# CAN.net
KiCad netlist of a schematic drawn in Altium Designer
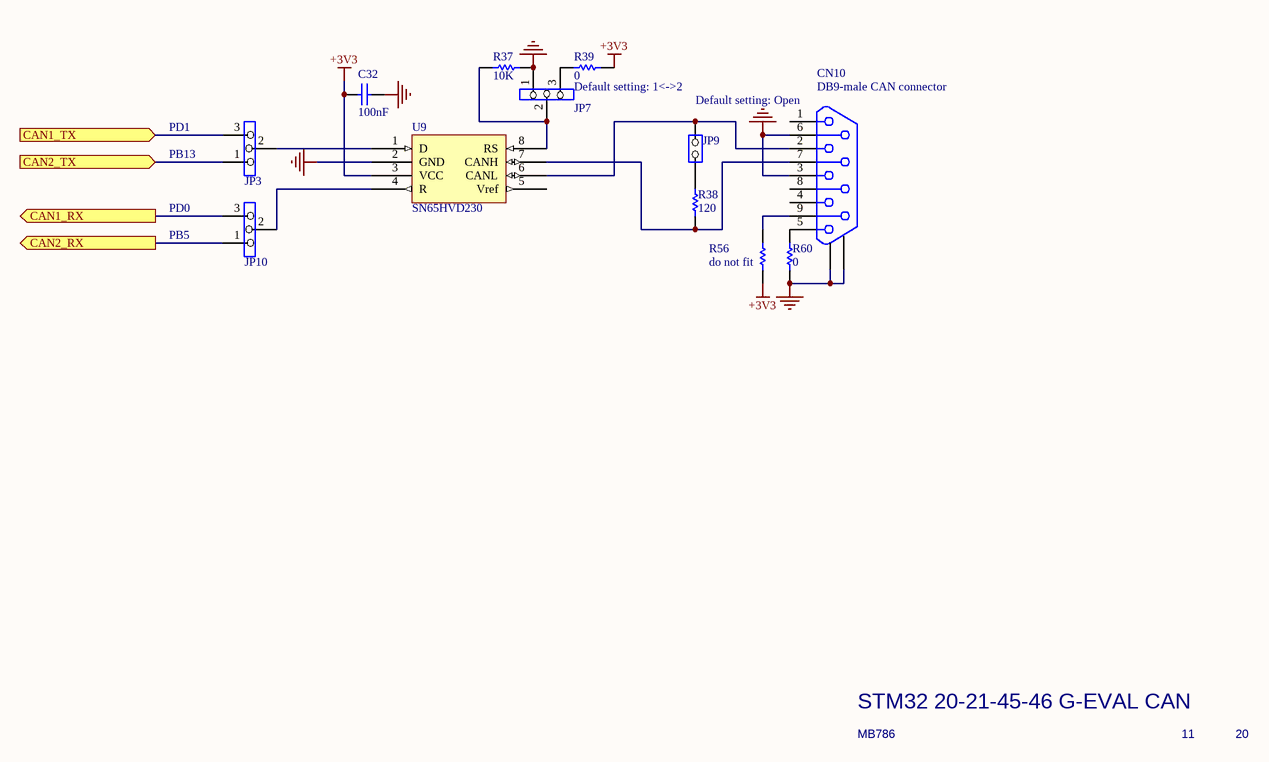
[diagram p0: CAN.SchDoc]

(export (version "E")
  (design (tool "Eeschema 10.0.6"))
  (components
    (comp (ref "C32")
      (value "100nF")
      (footprint "0402C")
      (description "Capacitor")
      (fields (field (name "PUBLISHER") "Altium Limited"))
      (libsource (lib "Miscellaneous Devices") (part "CAP"))
    )
    (comp (ref "CN10")
      (value "DB9-male CAN connector")
      (footprint "DB9/M")
      (libsource (lib "*") (part "DB9"))
    )
    (comp (ref "JP3") (value "~") (footprint "SIP3") (libsource (lib "STR910_SCHLIB") (part "Jumper3")))
    (comp (ref "JP7") (value "~") (footprint "SIP3") (libsource (lib "STR910_SCHLIB") (part "Jumper3")))
    (comp (ref "JP9") (value "~") (footprint "SIP2") (libsource (lib "*") (part "JP2")))
    (comp (ref "JP10") (value "~") (footprint "SIP3") (libsource (lib "STR910_SCHLIB") (part "Jumper3")))
    (comp (ref "R37")
      (value "10K")
      (footprint "0402R")
      (description "Resistor")
      (fields (field (name "PUBLISHER") "Altium Limited"))
      (libsource (lib "Miscellaneous Devices") (part "res1"))
    )
    (comp (ref "R38")
      (value "120")
      (footprint "0603R")
      (description "Resistor")
      (fields (field (name "PUBLISHER") "Altium Limited"))
      (libsource (lib "Miscellaneous Devices") (part "res1"))
    )
    (comp (ref "R39")
      (value "0")
      (footprint "0603R")
      (description "Resistor")
      (fields (field (name "PUBLISHER") "Altium Limited"))
      (libsource (lib "Miscellaneous Devices") (part "res1"))
    )
    (comp (ref "R56")
      (value "do not fit")
      (footprint "0603R")
      (description "Resistor")
      (fields (field (name "PUBLISHER") "Altium Limited"))
      (libsource (lib "Miscellaneous Devices") (part "res1"))
    )
    (comp (ref "R60")
      (value "0")
      (footprint "0603R")
      (description "Resistor")
      (fields (field (name "PUBLISHER") "Altium Limited"))
      (libsource (lib "Miscellaneous Devices") (part "res1"))
    )
    (comp (ref "U9")
      (value "SN65HVD230")
      (footprint "SO8")
      (libsource (lib "STR910_SCHLIB") (part "SN65HVD230D"))
    )
  )
  (nets
    (net (code "1") (name "+3V3") (class "Default")
      (node (ref "C32") (pin "2") (pinfunction "2_2") (pintype "passive"))
      (node (ref "R39") (pin "2") (pinfunction "2_2") (pintype "passive"))
      (node (ref "R56") (pin "1") (pinfunction "1_1") (pintype "passive"))
      (node (ref "U9") (pin "3") (pinfunction "VCC_3") (pintype "power_in"))
    )
    (net (code "2") (name "/CAN1_RX") (class "Default") (node (ref "JP10") (pin "3") (pintype "passive")))
    (net (code "3") (name "/CAN1_TX") (class "Default") (node (ref "JP3") (pin "3") (pintype "passive")))
    (net (code "4") (name "/CAN2_RX") (class "Default") (node (ref "JP10") (pin "1") (pintype "passive")))
    (net (code "5") (name "/CAN2_TX") (class "Default") (node (ref "JP3") (pin "1") (pintype "passive")))
    (net (code "6") (name "GND") (class "Default")
      (node (ref "C32") (pin "1") (pinfunction "1_1") (pintype "passive"))
      (node (ref "CN10") (pin "0") (pinfunction "0_0") (pintype "passive"))
      (node (ref "CN10") (pin "3") (pinfunction "3_3") (pintype "passive"))
      (node (ref "CN10") (pin "6") (pinfunction "6_6") (pintype "passive"))
      (node (ref "JP7") (pin "1") (pintype "passive"))
      (node (ref "R37") (pin "2") (pinfunction "2_2") (pintype "passive"))
      (node (ref "R60") (pin "1") (pinfunction "1_1") (pintype "passive"))
      (node (ref "U9") (pin "2") (pinfunction "GND_2") (pintype "power_in"))
    )
    (net (code "7") (name "Net-(CN10-Pad5)") (class "Default")
      (node (ref "CN10") (pin "5") (pinfunction "5_5") (pintype "passive"))
      (node (ref "R60") (pin "2") (pinfunction "2_2") (pintype "passive"))
    )
    (net (code "8") (name "Net-(CN10-Pad9)") (class "Default")
      (node (ref "CN10") (pin "9") (pinfunction "9_9") (pintype "passive"))
      (node (ref "R56") (pin "2") (pinfunction "2_2") (pintype "passive"))
    )
    (net (code "9") (name "Net-(JP7-Pad3)") (class "Default")
      (node (ref "JP7") (pin "3") (pintype "passive"))
      (node (ref "R39") (pin "1") (pinfunction "1_1") (pintype "passive"))
    )
    (net (code "10") (name "Net-(JP9-COMMON)") (class "Default")
      (node (ref "JP9") (pin "1") (pinfunction "COMMON_1") (pintype "passive"))
      (node (ref "R38") (pin "2") (pinfunction "2_2") (pintype "passive"))
    )
    (net (code "11") (name "Net-(JP9-NO)") (class "Default")
      (node (ref "CN10") (pin "2") (pinfunction "2_2") (pintype "passive"))
      (node (ref "JP9") (pin "2") (pinfunction "NO_2") (pintype "passive"))
      (node (ref "U9") (pin "6") (pinfunction "CANL_6") (pintype "bidirectional"))
    )
    (net (code "12") (name "Net-(U9-CANH)") (class "Default")
      (node (ref "CN10") (pin "7") (pinfunction "7_7") (pintype "passive"))
      (node (ref "R38") (pin "1") (pinfunction "1_1") (pintype "passive"))
      (node (ref "U9") (pin "7") (pinfunction "CANH_7") (pintype "bidirectional"))
    )
    (net (code "13") (name "Net-(U9-D)") (class "Default")
      (node (ref "JP3") (pin "2") (pintype "passive"))
      (node (ref "U9") (pin "1") (pinfunction "D_1") (pintype "input"))
    )
    (net (code "14") (name "Net-(U9-R)") (class "Default")
      (node (ref "JP10") (pin "2") (pintype "passive"))
      (node (ref "U9") (pin "4") (pinfunction "R_4") (pintype "output"))
    )
    (net (code "15") (name "Net-(U9-RS)") (class "Default")
      (node (ref "JP7") (pin "2") (pintype "passive"))
      (node (ref "R37") (pin "1") (pinfunction "1_1") (pintype "passive"))
      (node (ref "U9") (pin "8") (pinfunction "RS_8") (pintype "input"))
    )
    (net (code "16") (name "unconnected-(CN10-Pad1)") (class "Default")
      (node (ref "CN10") (pin "1") (pinfunction "1_1") (pintype "passive"))
    )
    (net (code "17") (name "unconnected-(CN10-Pad4)") (class "Default")
      (node (ref "CN10") (pin "4") (pinfunction "4_4") (pintype "passive"))
    )
    (net (code "18") (name "unconnected-(CN10-Pad8)") (class "Default")
      (node (ref "CN10") (pin "8") (pinfunction "8_8") (pintype "passive"))
    )
    (net (code "19") (name "unconnected-(U9-Vref-Pad5)") (class "Default")
      (node (ref "U9") (pin "5") (pinfunction "Vref_5") (pintype "output"))
    )
  )
)
